# ESP_NOW_uni_FULL.net
KiCad netlist of a schematic drawn in EAGLE
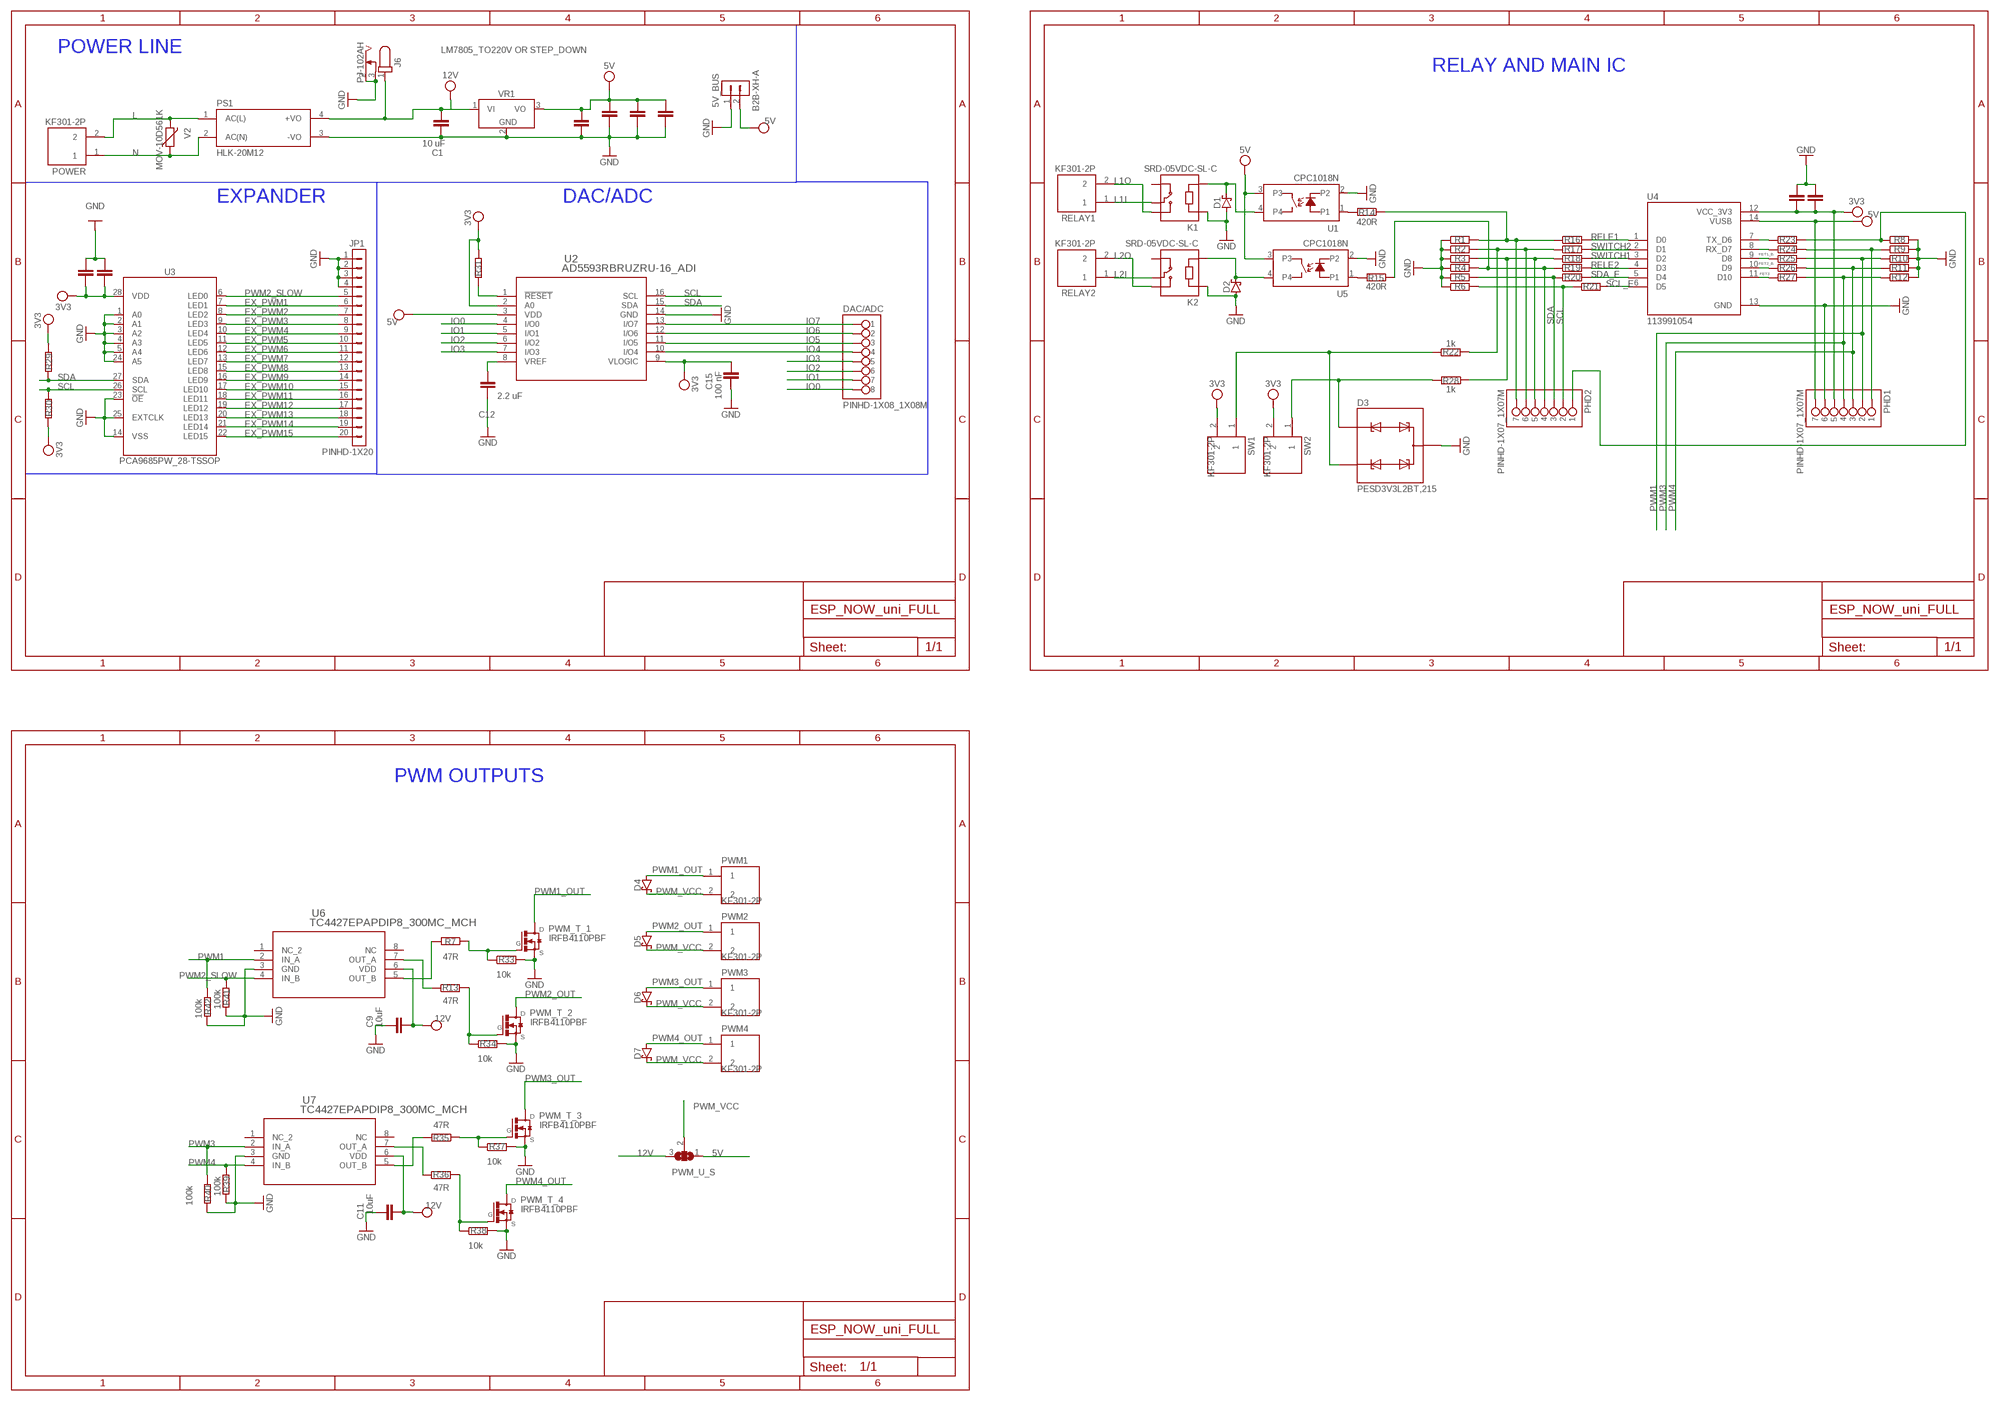
[diagram p0: schematic, sheet 1]

(export (version "E")
  (design (tool "Eeschema 10.0.6"))
  (components
    (comp (ref "5V_BUS")
      (value "B2B-XH-A")
      (footprint "eagle-import:B2B-XH-A")
      (fields (field (name "MANUFACTURER") "JST Sales America Inc."))
      (libsource (lib "eagle-import") (part "B2B-XH-A"))
    )
    (comp (ref "C1")
      (value "10 uF")
      (footprint "eagle-import:CAPC2012X110")
      (libsource (lib "eagle-import") (part "CCHIP-0805(2012-METRIC)_"))
    )
    (comp (ref "C2")
      (value "0.1uF")
      (footprint "eagle-import:CAPC2012X110")
      (libsource (lib "eagle-import") (part "CCHIP-0805(2012-METRIC)_"))
    )
    (comp (ref "C3")
      (value "10uF")
      (footprint "eagle-import:CAPC2012X110")
      (libsource (lib "eagle-import") (part "CCHIP-0805(2012-METRIC)_"))
    )
    (comp (ref "C4")
      (value "10uF")
      (footprint "eagle-import:CAPC2012X110")
      (libsource (lib "eagle-import") (part "CCHIP-0805(2012-METRIC)_"))
    )
    (comp (ref "C5")
      (value "10uF")
      (footprint "eagle-import:CAPC2012X110")
      (libsource (lib "eagle-import") (part "CCHIP-0805(2012-METRIC)_"))
    )
    (comp (ref "C6")
      (value "10uF")
      (footprint "eagle-import:CAPC2012X110")
      (libsource (lib "eagle-import") (part "CCHIP-0805(2012-METRIC)_"))
    )
    (comp (ref "C7")
      (value "10uF")
      (footprint "eagle-import:CAPC2012X110")
      (libsource (lib "eagle-import") (part "CCHIP-0805(2012-METRIC)_"))
    )
    (comp (ref "C8")
      (value "10uF")
      (footprint "eagle-import:CAPC2012X110")
      (libsource (lib "eagle-import") (part "CCHIP-0805(2012-METRIC)_"))
    )
    (comp (ref "C9")
      (value "10uF")
      (footprint "eagle-import:CAPC2012X110")
      (libsource (lib "eagle-import") (part "CCHIP-0805(2012-METRIC)_"))
    )
    (comp (ref "C10")
      (value "10uF")
      (footprint "eagle-import:CAPC2012X110")
      (libsource (lib "eagle-import") (part "CCHIP-0805(2012-METRIC)_"))
    )
    (comp (ref "C11")
      (value "10uF")
      (footprint "eagle-import:CAPC2012X110")
      (libsource (lib "eagle-import") (part "CCHIP-0805(2012-METRIC)_"))
    )
    (comp (ref "C12")
      (value "2.2 uF")
      (footprint "eagle-import:CAPC2012X110")
      (libsource (lib "eagle-import") (part "CCHIP-0805(2012-METRIC)_"))
    )
    (comp (ref "C15")
      (value "100 nF")
      (footprint "eagle-import:CAPC2012X110")
      (libsource (lib "eagle-import") (part "CCHIP-0805(2012-METRIC)_"))
    )
    (comp (ref "D1")
      (value "SCHOTTKY_MBR0520LT1GDO-219")
      (footprint "eagle-import:SODFL3718X115")
      (fields (field (name "MANUFACTURER") "onsemi") (field (name "MPN") "MBR0520LT1G"))
      (libsource (lib "eagle-import") (part "SCHOTTKY_DO-219MBR0520LT1G"))
    )
    (comp (ref "D2")
      (value "SCHOTTKY_MBR0520LT1GDO-219")
      (footprint "eagle-import:SODFL3718X115")
      (fields (field (name "MANUFACTURER") "onsemi") (field (name "MPN") "MBR0520LT1G"))
      (libsource (lib "eagle-import") (part "SCHOTTKY_DO-219MBR0520LT1G"))
    )
    (comp (ref "D3")
      (value "PESD3V3L2BT,215")
      (footprint "eagle-import:SOT95P230X110-3N")
      (fields (field (name "MF") "NXP Semiconductors"))
      (libsource (lib "eagle-import") (part "PESD3V3L2BT,215"))
    )
    (comp (ref "D4")
      (value "SCHOTTKY_MBR0520LT1GDO-219")
      (footprint "eagle-import:SODFL3718X115")
      (fields (field (name "MANUFACTURER") "onsemi") (field (name "MPN") "MBR0520LT1G"))
      (libsource (lib "eagle-import") (part "SCHOTTKY_DO-219MBR0520LT1G"))
    )
    (comp (ref "D5")
      (value "SCHOTTKY_MBR0520LT1GDO-219")
      (footprint "eagle-import:SODFL3718X115")
      (fields (field (name "MANUFACTURER") "onsemi") (field (name "MPN") "MBR0520LT1G"))
      (libsource (lib "eagle-import") (part "SCHOTTKY_DO-219MBR0520LT1G"))
    )
    (comp (ref "D6")
      (value "SCHOTTKY_MBR0520LT1GDO-219")
      (footprint "eagle-import:SODFL3718X115")
      (fields (field (name "MANUFACTURER") "onsemi") (field (name "MPN") "MBR0520LT1G"))
      (libsource (lib "eagle-import") (part "SCHOTTKY_DO-219MBR0520LT1G"))
    )
    (comp (ref "D7")
      (value "SCHOTTKY_MBR0520LT1GDO-219")
      (footprint "eagle-import:SODFL3718X115")
      (fields (field (name "MANUFACTURER") "onsemi") (field (name "MPN") "MBR0520LT1G"))
      (libsource (lib "eagle-import") (part "SCHOTTKY_DO-219MBR0520LT1G"))
    )
    (comp (ref "DAC/ADC")
      (value "PINHD-1X08_1X08M")
      (footprint "eagle-import:1X08")
      (libsource (lib "eagle-import") (part "PINHD-1X08_1X08M"))
    )
    (comp (ref "J6")
      (value "PJ-102AH")
      (footprint "eagle-import:PJ-102AH")
      (fields (field (name "MANUFACTURER") "Same Sky"))
      (libsource (lib "eagle-import") (part "PJ-102AH"))
    )
    (comp (ref "JP1")
      (value "PINHD-1X20")
      (footprint "eagle-import:1X20")
      (libsource (lib "eagle-import") (part "PINHD-1X20"))
    )
    (comp (ref "K1")
      (value "SRD-05VDC-SL-C")
      (footprint "eagle-import:RELAY_SRD-05VDC-SL-C")
      (fields (field (name "MF") "Songle Relay"))
      (libsource (lib "eagle-import") (part "SRD-05VDC-SL-C"))
    )
    (comp (ref "K2")
      (value "SRD-05VDC-SL-C")
      (footprint "eagle-import:RELAY_SRD-05VDC-SL-C")
      (fields (field (name "MF") "Songle Relay"))
      (libsource (lib "eagle-import") (part "SRD-05VDC-SL-C"))
    )
    (comp (ref "PHD1")
      (value "PINHD-1X07_1X07M")
      (footprint "eagle-import:1X07")
      (libsource (lib "eagle-import") (part "PINHD-1X07_1X07M"))
    )
    (comp (ref "PHD2")
      (value "PINHD-1X07_1X07M")
      (footprint "eagle-import:1X07")
      (libsource (lib "eagle-import") (part "PINHD-1X07_1X07M"))
    )
    (comp (ref "POWER")
      (value "KF301-2P")
      (footprint "eagle-import:HANDSON_KF301-2P")
      (fields (field (name "MF") "Handson Technology"))
      (libsource (lib "eagle-import") (part "KF301-2P"))
    )
    (comp (ref "PS1")
      (value "HLK-20M12")
      (footprint "eagle-import:CONV_HLK-20M12")
      (fields (field (name "MF") "Hi-link"))
      (libsource (lib "eagle-import") (part "HLK-20M12"))
    )
    (comp (ref "PWM1")
      (value "KF301-2P")
      (footprint "eagle-import:HANDSON_KF301-2P")
      (fields (field (name "MF") "Handson Technology"))
      (libsource (lib "eagle-import") (part "KF301-2P"))
    )
    (comp (ref "PWM2")
      (value "KF301-2P")
      (footprint "eagle-import:HANDSON_KF301-2P")
      (fields (field (name "MF") "Handson Technology"))
      (libsource (lib "eagle-import") (part "KF301-2P"))
    )
    (comp (ref "PWM3")
      (value "KF301-2P")
      (footprint "eagle-import:HANDSON_KF301-2P")
      (fields (field (name "MF") "Handson Technology"))
      (libsource (lib "eagle-import") (part "KF301-2P"))
    )
    (comp (ref "PWM4")
      (value "KF301-2P")
      (footprint "eagle-import:HANDSON_KF301-2P")
      (fields (field (name "MF") "Handson Technology"))
      (libsource (lib "eagle-import") (part "KF301-2P"))
    )
    (comp (ref "PWM_T_1")
      (value "IRFB4110PBF")
      (footprint "eagle-import:TO220V")
      (fields (field (name "MF") "Infineon Technologies") (field (name "MP") "IRL540N"))
      (libsource (lib "eagle-import") (part "IRL540N"))
    )
    (comp (ref "PWM_T_2")
      (value "IRFB4110PBF")
      (footprint "eagle-import:TO220V")
      (fields (field (name "MF") "Infineon Technologies") (field (name "MP") "IRL540N"))
      (libsource (lib "eagle-import") (part "IRL540N"))
    )
    (comp (ref "PWM_T_3")
      (value "IRFB4110PBF")
      (footprint "eagle-import:TO220V")
      (fields (field (name "MF") "Infineon Technologies") (field (name "MP") "IRL540N"))
      (libsource (lib "eagle-import") (part "IRL540N"))
    )
    (comp (ref "PWM_T_4")
      (value "IRFB4110PBF")
      (footprint "eagle-import:TO220V")
      (fields (field (name "MF") "Infineon Technologies") (field (name "MP") "IRL540N"))
      (libsource (lib "eagle-import") (part "IRL540N"))
    )
    (comp (ref "PWM_U_S")
      (value "SJ2W")
      (footprint "eagle-import:SJ_2")
      (libsource (lib "eagle-import") (part "SJ2W"))
    )
    (comp (ref "R1")
      (value "R_CHIP-0603(1608-METRIC)")
      (footprint "eagle-import:RESC1608X60")
      (libsource (lib "eagle-import") (part "RCHIP-0603(1608-METRIC)_"))
    )
    (comp (ref "R2")
      (value "R_CHIP-0603(1608-METRIC)")
      (footprint "eagle-import:RESC1608X60")
      (libsource (lib "eagle-import") (part "RCHIP-0603(1608-METRIC)_"))
    )
    (comp (ref "R3")
      (value "R_CHIP-0603(1608-METRIC)")
      (footprint "eagle-import:RESC1608X60")
      (libsource (lib "eagle-import") (part "RCHIP-0603(1608-METRIC)_"))
    )
    (comp (ref "R4")
      (value "R_CHIP-0603(1608-METRIC)")
      (footprint "eagle-import:RESC1608X60")
      (libsource (lib "eagle-import") (part "RCHIP-0603(1608-METRIC)_"))
    )
    (comp (ref "R5")
      (value "R_CHIP-0603(1608-METRIC)")
      (footprint "eagle-import:RESC1608X60")
      (libsource (lib "eagle-import") (part "RCHIP-0603(1608-METRIC)_"))
    )
    (comp (ref "R6")
      (value "R_CHIP-0603(1608-METRIC)")
      (footprint "eagle-import:RESC1608X60")
      (libsource (lib "eagle-import") (part "RCHIP-0603(1608-METRIC)_"))
    )
    (comp (ref "R7")
      (value "47R")
      (footprint "eagle-import:RESC1608X60")
      (libsource (lib "eagle-import") (part "RCHIP-0603(1608-METRIC)_"))
    )
    (comp (ref "R8")
      (value "R_CHIP-0603(1608-METRIC)")
      (footprint "eagle-import:RESC1608X60")
      (libsource (lib "eagle-import") (part "RCHIP-0603(1608-METRIC)_"))
    )
    (comp (ref "R9")
      (value "R_CHIP-0603(1608-METRIC)")
      (footprint "eagle-import:RESC1608X60")
      (libsource (lib "eagle-import") (part "RCHIP-0603(1608-METRIC)_"))
    )
    (comp (ref "R10")
      (value "R_CHIP-0603(1608-METRIC)")
      (footprint "eagle-import:RESC1608X60")
      (libsource (lib "eagle-import") (part "RCHIP-0603(1608-METRIC)_"))
    )
    (comp (ref "R11")
      (value "R_CHIP-0603(1608-METRIC)")
      (footprint "eagle-import:RESC1608X60")
      (libsource (lib "eagle-import") (part "RCHIP-0603(1608-METRIC)_"))
    )
    (comp (ref "R12")
      (value "R_CHIP-0603(1608-METRIC)")
      (footprint "eagle-import:RESC1608X60")
      (libsource (lib "eagle-import") (part "RCHIP-0603(1608-METRIC)_"))
    )
    (comp (ref "R13")
      (value "47R")
      (footprint "eagle-import:RESC1608X60")
      (libsource (lib "eagle-import") (part "RCHIP-0603(1608-METRIC)_"))
    )
    (comp (ref "R14")
      (value "420R")
      (footprint "eagle-import:RESC1608X60")
      (libsource (lib "eagle-import") (part "RCHIP-0603(1608-METRIC)_"))
    )
    (comp (ref "R15")
      (value "420R")
      (footprint "eagle-import:RESC1608X60")
      (libsource (lib "eagle-import") (part "RCHIP-0603(1608-METRIC)_"))
    )
    (comp (ref "R16")
      (value "R_CHIP-0603(1608-METRIC)")
      (footprint "eagle-import:RESC1608X60")
      (libsource (lib "eagle-import") (part "RCHIP-0603(1608-METRIC)_"))
    )
    (comp (ref "R17")
      (value "R_CHIP-0603(1608-METRIC)")
      (footprint "eagle-import:RESC1608X60")
      (libsource (lib "eagle-import") (part "RCHIP-0603(1608-METRIC)_"))
    )
    (comp (ref "R18")
      (value "R_CHIP-0603(1608-METRIC)")
      (footprint "eagle-import:RESC1608X60")
      (libsource (lib "eagle-import") (part "RCHIP-0603(1608-METRIC)_"))
    )
    (comp (ref "R19")
      (value "R_CHIP-0603(1608-METRIC)")
      (footprint "eagle-import:RESC1608X60")
      (libsource (lib "eagle-import") (part "RCHIP-0603(1608-METRIC)_"))
    )
    (comp (ref "R20")
      (value "R_CHIP-0603(1608-METRIC)")
      (footprint "eagle-import:RESC1608X60")
      (libsource (lib "eagle-import") (part "RCHIP-0603(1608-METRIC)_"))
    )
    (comp (ref "R21")
      (value "R_CHIP-0603(1608-METRIC)")
      (footprint "eagle-import:RESC1608X60")
      (libsource (lib "eagle-import") (part "RCHIP-0603(1608-METRIC)_"))
    )
    (comp (ref "R22")
      (value "1k")
      (footprint "eagle-import:RESC1608X60")
      (libsource (lib "eagle-import") (part "RCHIP-0603(1608-METRIC)_"))
    )
    (comp (ref "R23")
      (value "R_CHIP-0603(1608-METRIC)")
      (footprint "eagle-import:RESC1608X60")
      (libsource (lib "eagle-import") (part "RCHIP-0603(1608-METRIC)_"))
    )
    (comp (ref "R24")
      (value "R_CHIP-0603(1608-METRIC)")
      (footprint "eagle-import:RESC1608X60")
      (libsource (lib "eagle-import") (part "RCHIP-0603(1608-METRIC)_"))
    )
    (comp (ref "R25")
      (value "R_CHIP-0603(1608-METRIC)")
      (footprint "eagle-import:RESC1608X60")
      (libsource (lib "eagle-import") (part "RCHIP-0603(1608-METRIC)_"))
    )
    (comp (ref "R26")
      (value "R_CHIP-0603(1608-METRIC)")
      (footprint "eagle-import:RESC1608X60")
      (libsource (lib "eagle-import") (part "RCHIP-0603(1608-METRIC)_"))
    )
    (comp (ref "R27")
      (value "R_CHIP-0603(1608-METRIC)")
      (footprint "eagle-import:RESC1608X60")
      (libsource (lib "eagle-import") (part "RCHIP-0603(1608-METRIC)_"))
    )
    (comp (ref "R28")
      (value "1k")
      (footprint "eagle-import:RESC1608X60")
      (libsource (lib "eagle-import") (part "RCHIP-0603(1608-METRIC)_"))
    )
    (comp (ref "R29")
      (value "R_CHIP-0603(1608-METRIC)")
      (footprint "eagle-import:RESC1608X60")
      (libsource (lib "eagle-import") (part "RCHIP-0603(1608-METRIC)_"))
    )
    (comp (ref "R30")
      (value "R_CHIP-0603(1608-METRIC)")
      (footprint "eagle-import:RESC1608X60")
      (libsource (lib "eagle-import") (part "RCHIP-0603(1608-METRIC)_"))
    )
    (comp (ref "R31")
      (value "R_CHIP-0603(1608-METRIC)")
      (footprint "eagle-import:RESC1608X60")
      (libsource (lib "eagle-import") (part "RCHIP-0603(1608-METRIC)_"))
    )
    (comp (ref "R33")
      (value "10k")
      (footprint "eagle-import:RESC1608X60")
      (libsource (lib "eagle-import") (part "RCHIP-0603(1608-METRIC)_"))
    )
    (comp (ref "R34")
      (value "10k")
      (footprint "eagle-import:RESC1608X60")
      (libsource (lib "eagle-import") (part "RCHIP-0603(1608-METRIC)_"))
    )
    (comp (ref "R35")
      (value "47R")
      (footprint "eagle-import:RESC1608X60")
      (libsource (lib "eagle-import") (part "RCHIP-0603(1608-METRIC)_"))
    )
    (comp (ref "R36")
      (value "47R")
      (footprint "eagle-import:RESC1608X60")
      (libsource (lib "eagle-import") (part "RCHIP-0603(1608-METRIC)_"))
    )
    (comp (ref "R37")
      (value "10k")
      (footprint "eagle-import:RESC1608X60")
      (libsource (lib "eagle-import") (part "RCHIP-0603(1608-METRIC)_"))
    )
    (comp (ref "R38")
      (value "10k")
      (footprint "eagle-import:RESC1608X60")
      (libsource (lib "eagle-import") (part "RCHIP-0603(1608-METRIC)_"))
    )
    (comp (ref "R39")
      (value "100k")
      (footprint "eagle-import:RESC1608X60")
      (libsource (lib "eagle-import") (part "RCHIP-0603(1608-METRIC)_"))
    )
    (comp (ref "R40")
      (value "100k")
      (footprint "eagle-import:RESC1608X60")
      (libsource (lib "eagle-import") (part "RCHIP-0603(1608-METRIC)_"))
    )
    (comp (ref "R41")
      (value "100k")
      (footprint "eagle-import:RESC1608X60")
      (libsource (lib "eagle-import") (part "RCHIP-0603(1608-METRIC)_"))
    )
    (comp (ref "R42")
      (value "100k")
      (footprint "eagle-import:RESC1608X60")
      (libsource (lib "eagle-import") (part "RCHIP-0603(1608-METRIC)_"))
    )
    (comp (ref "RELAY1")
      (value "KF301-2P")
      (footprint "eagle-import:HANDSON_KF301-2P")
      (fields (field (name "MF") "Handson Technology"))
      (libsource (lib "eagle-import") (part "KF301-2P"))
    )
    (comp (ref "RELAY2")
      (value "KF301-2P")
      (footprint "eagle-import:HANDSON_KF301-2P")
      (fields (field (name "MF") "Handson Technology"))
      (libsource (lib "eagle-import") (part "KF301-2P"))
    )
    (comp (ref "SW1")
      (value "KF301-2P")
      (footprint "eagle-import:HANDSON_KF301-2P")
      (fields (field (name "MF") "Handson Technology"))
      (libsource (lib "eagle-import") (part "KF301-2P"))
    )
    (comp (ref "SW2")
      (value "KF301-2P")
      (footprint "eagle-import:HANDSON_KF301-2P")
      (fields (field (name "MF") "Handson Technology"))
      (libsource (lib "eagle-import") (part "KF301-2P"))
    )
    (comp (ref "U1")
      (value "CPC1018N")
      (footprint "eagle-import:CLARE_SO4")
      (fields (field (name "MF") "IXYS Integrated Circuits"))
      (libsource (lib "eagle-import") (part "CPC1018N"))
    )
    (comp (ref "U2")
      (value "AD5593RBRUZRU-16_ADI")
      (footprint "eagle-import:RU-16_ADI")
      (fields
        (field (name "MANUFACTURER_PART_NUMBER") "AD5593RBRUZ")
        (field (name "COPYRIGHT") "Copyright (C) 2026 Ultra Librarian. All rights reserved.")
      )
      (libsource (lib "eagle-import") (part "AD5593RBRUZRU-16_ADI"))
    )
    (comp (ref "U3")
      (value "PCA9685PW_28-TSSOP")
      (footprint "eagle-import:SOP65P640X110-28")
      (fields (field (name "MANUFACTURER") "NXP USA Inc.") (field (name "MPN") "PCA9685PW118"))
      (libsource (lib "eagle-import") (part "PCA9685PW_28-TSSOP"))
    )
    (comp (ref "U4")
      (value "113991054")
      (footprint "eagle-import:MODULE_113991054")
      (fields (field (name "MF") "Seeed Technology Co., Ltd"))
      (libsource (lib "eagle-import") (part "113991054"))
    )
    (comp (ref "U5")
      (value "CPC1018N")
      (footprint "eagle-import:CLARE_SO4")
      (fields (field (name "MF") "IXYS Integrated Circuits"))
      (libsource (lib "eagle-import") (part "CPC1018N"))
    )
    (comp (ref "U6")
      (value "TC4427EPAPDIP8_300MC_MCH")
      (footprint "eagle-import:PDIP8_300MC_MCH")
      (fields
        (field (name "MANUFACTURER_PART_NUMBER") "TC4427EPA")
        (field (name "COPYRIGHT") "Copyright (C) 2026 Ultra Librarian. All rights reserved.")
      )
      (libsource (lib "eagle-import") (part "TC4427EPAPDIP8_300MC_MCH"))
    )
    (comp (ref "U7")
      (value "TC4427EPAPDIP8_300MC_MCH")
      (footprint "eagle-import:PDIP8_300MC_MCH")
      (fields
        (field (name "MANUFACTURER_PART_NUMBER") "TC4427EPA")
        (field (name "COPYRIGHT") "Copyright (C) 2026 Ultra Librarian. All rights reserved.")
      )
      (libsource (lib "eagle-import") (part "TC4427EPAPDIP8_300MC_MCH"))
    )
    (comp (ref "V2")
      (value "MOV-10D561K")
      (footprint "eagle-import:MOV-10D561")
      (fields (field (name "MF") "Bourns"))
      (libsource (lib "eagle-import") (part "MOV-10D561K"))
    )
    (comp (ref "VR1")
      (value "LM7805_TO220V OR STEP_DOWN")
      (footprint "eagle-import:TO220V")
      (libsource (lib "eagle-import") (part "LM7805_TO220V"))
    )
  )
  (nets
    (net (code "1") (name "/EX_PWM1") (class "Default")
      (node (ref "JP1") (pin "6") (pinfunction "6_6") (pintype "passive"))
      (node (ref "U3") (pin "7") (pinfunction "LED1_7") (pintype "passive"))
    )
    (net (code "2") (name "/EX_PWM2") (class "Default")
      (node (ref "JP1") (pin "7") (pinfunction "7_7") (pintype "passive"))
      (node (ref "U3") (pin "8") (pinfunction "LED2_8") (pintype "passive"))
    )
    (net (code "3") (name "/EX_PWM3") (class "Default")
      (node (ref "JP1") (pin "8") (pinfunction "8_8") (pintype "passive"))
      (node (ref "U3") (pin "9") (pinfunction "LED3_9") (pintype "passive"))
    )
    (net (code "4") (name "/EX_PWM4") (class "Default")
      (node (ref "JP1") (pin "9") (pinfunction "9_9") (pintype "passive"))
      (node (ref "U3") (pin "10") (pinfunction "LED4_10") (pintype "passive"))
    )
    (net (code "5") (name "/EX_PWM5") (class "Default")
      (node (ref "JP1") (pin "10") (pinfunction "10_10") (pintype "passive"))
      (node (ref "U3") (pin "11") (pinfunction "LED5_11") (pintype "passive"))
    )
    (net (code "6") (name "/EX_PWM6") (class "Default")
      (node (ref "JP1") (pin "11") (pinfunction "11_11") (pintype "passive"))
      (node (ref "U3") (pin "12") (pinfunction "LED6_12") (pintype "passive"))
    )
    (net (code "7") (name "/EX_PWM7") (class "Default")
      (node (ref "JP1") (pin "12") (pinfunction "12_12") (pintype "passive"))
      (node (ref "U3") (pin "13") (pinfunction "LED7_13") (pintype "passive"))
    )
    (net (code "8") (name "/EX_PWM8") (class "Default")
      (node (ref "JP1") (pin "13") (pinfunction "13_13") (pintype "passive"))
      (node (ref "U3") (pin "15") (pinfunction "LED8_15") (pintype "passive"))
    )
    (net (code "9") (name "/EX_PWM9") (class "Default")
      (node (ref "JP1") (pin "14") (pinfunction "14_14") (pintype "passive"))
      (node (ref "U3") (pin "16") (pinfunction "LED9_16") (pintype "passive"))
    )
    (net (code "10") (name "/EX_PWM10") (class "Default")
      (node (ref "JP1") (pin "15") (pinfunction "15_15") (pintype "passive"))
      (node (ref "U3") (pin "17") (pinfunction "LED10_17") (pintype "passive"))
    )
    (net (code "11") (name "/EX_PWM11") (class "Default")
      (node (ref "JP1") (pin "16") (pinfunction "16_16") (pintype "passive"))
      (node (ref "U3") (pin "18") (pinfunction "LED11_18") (pintype "passive"))
    )
    (net (code "12") (name "/EX_PWM12") (class "Default")
      (node (ref "JP1") (pin "17") (pinfunction "17_17") (pintype "passive"))
      (node (ref "U3") (pin "19") (pinfunction "LED12_19") (pintype "passive"))
    )
    (net (code "13") (name "/EX_PWM13") (class "Default")
      (node (ref "JP1") (pin "18") (pinfunction "18_18") (pintype "passive"))
      (node (ref "U3") (pin "20") (pinfunction "LED13_20") (pintype "passive"))
    )
    (net (code "14") (name "/EX_PWM14") (class "Default")
      (node (ref "JP1") (pin "19") (pinfunction "19_19") (pintype "passive"))
      (node (ref "U3") (pin "21") (pinfunction "LED14_21") (pintype "passive"))
    )
    (net (code "15") (name "/EX_PWM15") (class "Default")
      (node (ref "JP1") (pin "20") (pinfunction "20_20") (pintype "passive"))
      (node (ref "U3") (pin "22") (pinfunction "LED15_22") (pintype "passive"))
    )
    (net (code "16") (name "/FET1_B") (class "Default")
      (node (ref "R25") (pin "1") (pinfunction "1_1") (pintype "passive"))
      (node (ref "U4") (pin "9") (pinfunction "D8_9") (pintype "bidirectional"))
    )
    (net (code "17") (name "/FET2_B") (class "Default")
      (node (ref "R26") (pin "1") (pinfunction "1_1") (pintype "passive"))
      (node (ref "U4") (pin "10") (pinfunction "D9_10") (pintype "bidirectional"))
    )
    (net (code "18") (name "/FET3") (class "Default")
      (node (ref "R27") (pin "1") (pinfunction "1_1") (pintype "passive"))
      (node (ref "U4") (pin "11") (pinfunction "D10_11") (pintype "bidirectional"))
    )
    (net (code "19") (name "/IO0") (class "Default")
      (node (ref "DAC/ADC") (pin "8") (pinfunction "8_8") (pintype "bidirectional"))
      (node (ref "U2") (pin "4") (pinfunction "I/O0_4") (pintype "passive"))
    )
    (net (code "20") (name "/IO1") (class "Default")
      (node (ref "DAC/ADC") (pin "7") (pinfunction "7_7") (pintype "bidirectional"))
      (node (ref "U2") (pin "5") (pinfunction "I/O1_5") (pintype "passive"))
    )
    (net (code "21") (name "/IO2") (class "Default")
      (node (ref "DAC/ADC") (pin "6") (pinfunction "6_6") (pintype "bidirectional"))
      (node (ref "U2") (pin "6") (pinfunction "I/O2_6") (pintype "passive"))
    )
    (net (code "22") (name "/IO3") (class "Default")
      (node (ref "DAC/ADC") (pin "5") (pinfunction "5_5") (pintype "bidirectional"))
      (node (ref "U2") (pin "7") (pinfunction "I/O3_7") (pintype "passive"))
    )
    (net (code "23") (name "/IO4") (class "Default")
      (node (ref "DAC/ADC") (pin "4") (pinfunction "4_4") (pintype "bidirectional"))
      (node (ref "U2") (pin "10") (pinfunction "I/O4_10") (pintype "passive"))
    )
    (net (code "24") (name "/IO5") (class "Default")
      (node (ref "DAC/ADC") (pin "3") (pinfunction "3_3") (pintype "bidirectional"))
      (node (ref "U2") (pin "11") (pinfunction "I/O5_11") (pintype "passive"))
    )
    (net (code "25") (name "/IO6") (class "Default")
      (node (ref "DAC/ADC") (pin "2") (pinfunction "2_2") (pintype "bidirectional"))
      (node (ref "U2") (pin "12") (pinfunction "I/O6_12") (pintype "passive"))
    )
    (net (code "26") (name "/IO7") (class "Default")
      (node (ref "DAC/ADC") (pin "1") (pinfunction "1_1") (pintype "bidirectional"))
      (node (ref "U2") (pin "13") (pinfunction "I/O7_13") (pintype "passive"))
    )
    (net (code "27") (name "/L") (class "Default")
      (node (ref "POWER") (pin "2") (pinfunction "2_2") (pintype "passive"))
      (node (ref "PS1") (pin "1") (pinfunction "AC(L)_1") (pintype "input"))
      (node (ref "V2") (pin "2") (pinfunction "2_2") (pintype "passive"))
    )
    (net (code "28") (name "/L1I") (class "Default")
      (node (ref "K1") (pin "COM") (pinfunction "COM_COM") (pintype "passive"))
      (node (ref "RELAY1") (pin "1") (pinfunction "1_1") (pintype "passive"))
    )
    (net (code "29") (name "/L1O") (class "Default")
      (node (ref "K1") (pin "NO") (pinfunction "NO_NO") (pintype "passive"))
      (node (ref "RELAY1") (pin "2") (pinfunction "2_2") (pintype "passive"))
    )
    (net (code "30") (name "/L2I") (class "Default")
      (node (ref "K2") (pin "COM") (pinfunction "COM_COM") (pintype "passive"))
      (node (ref "RELAY2") (pin "1") (pinfunction "1_1") (pintype "passive"))
    )
    (net (code "31") (name "/L2O") (class "Default")
      (node (ref "K2") (pin "NO") (pinfunction "NO_NO") (pintype "passive"))
      (node (ref "RELAY2") (pin "2") (pinfunction "2_2") (pintype "passive"))
    )
    (net (code "32") (name "/N") (class "Default")
      (node (ref "POWER") (pin "1") (pinfunction "1_1") (pintype "passive"))
      (node (ref "PS1") (pin "2") (pinfunction "AC(N)_2") (pintype "input"))
      (node (ref "V2") (pin "1") (pinfunction "1_1") (pintype "passive"))
    )
    (net (code "33") (name "/PWM1") (class "Default")
      (node (ref "PHD1") (pin "2") (pinfunction "2_2") (pintype "bidirectional"))
      (node (ref "R10") (pin "1") (pinfunction "1_1") (pintype "passive"))
      (node (ref "R25") (pin "2") (pinfunction "2_2") (pintype "passive"))
      (node (ref "R42") (pin "1") (pinfunction "1_1") (pintype "passive"))
      (node (ref "U6") (pin "2") (pinfunction "IN_A_2") (pintype "passive"))
    )
    (net (code "34") (name "/PWM1_OUT") (class "Default")
      (node (ref "D4") (pin "2") (pinfunction "A_2") (pintype "passive"))
      (node (ref "PWM1") (pin "1") (pinfunction "1_1") (pintype "passive"))
      (node (ref "PWM_T_1") (pin "2") (pinfunction "D_2") (pintype "passive"))
    )
    (net (code "35") (name "/PWM2_OUT") (class "Default")
      (node (ref "D5") (pin "2") (pinfunction "A_2") (pintype "passive"))
      (node (ref "PWM2") (pin "1") (pinfunction "1_1") (pintype "passive"))
      (node (ref "PWM_T_2") (pin "2") (pinfunction "D_2") (pintype "passive"))
    )
    (net (code "36") (name "/PWM2_SLOW") (class "Default")
      (node (ref "JP1") (pin "5") (pinfunction "5_5") (pintype "passive"))
      (node (ref "R41") (pin "1") (pinfunction "1_1") (pintype "passive"))
      (node (ref "U3") (pin "6") (pinfunction "LED0_6") (pintype "passive"))
      (node (ref "U6") (pin "4") (pinfunction "IN_B_4") (pintype "passive"))
    )
    (net (code "37") (name "/PWM3") (class "Default")
      (node (ref "PHD1") (pin "4") (pinfunction "4_4") (pintype "bidirectional"))
      (node (ref "R12") (pin "1") (pinfunction "1_1") (pintype "passive"))
      (node (ref "R27") (pin "2") (pinfunction "2_2") (pintype "passive"))
      (node (ref "R40") (pin "1") (pinfunction "1_1") (pintype "passive"))
      (node (ref "U7") (pin "2") (pinfunction "IN_A_2") (pintype "passive"))
    )
    (net (code "38") (name "/PWM3_OUT") (class "Default")
      (node (ref "D6") (pin "2") (pinfunction "A_2") (pintype "passive"))
      (node (ref "PWM3") (pin "1") (pinfunction "1_1") (pintype "passive"))
      (node (ref "PWM_T_3") (pin "2") (pinfunction "D_2") (pintype "passive"))
    )
    (net (code "39") (name "/PWM4") (class "Default")
      (node (ref "PHD1") (pin "3") (pinfunction "3_3") (pintype "bidirectional"))
      (node (ref "R11") (pin "1") (pinfunction "1_1") (pintype "passive"))
      (node (ref "R26") (pin "2") (pinfunction "2_2") (pintype "passive"))
      (node (ref "R39") (pin "1") (pinfunction "1_1") (pintype "passive"))
      (node (ref "U7") (pin "4") (pinfunction "IN_B_4") (pintype "passive"))
    )
    (net (code "40") (name "/PWM4_OUT") (class "Default")
      (node (ref "D7") (pin "2") (pinfunction "A_2") (pintype "passive"))
      (node (ref "PWM4") (pin "1") (pinfunction "1_1") (pintype "passive"))
      (node (ref "PWM_T_4") (pin "2") (pinfunction "D_2") (pintype "passive"))
    )
    (net (code "41") (name "/PWM_VCC") (class "Default")
      (node (ref "D4") (pin "1") (pinfunction "C_1") (pintype "passive"))
      (node (ref "D5") (pin "1") (pinfunction "C_1") (pintype "passive"))
      (node (ref "D6") (pin "1") (pinfunction "C_1") (pintype "passive"))
      (node (ref "D7") (pin "1") (pinfunction "C_1") (pintype "passive"))
      (node (ref "PWM1") (pin "2") (pinfunction "2_2") (pintype "passive"))
      (node (ref "PWM2") (pin "2") (pinfunction "2_2") (pintype "passive"))
      (node (ref "PWM3") (pin "2") (pinfunction "2_2") (pintype "passive"))
      (node (ref "PWM4") (pin "2") (pinfunction "2_2") (pintype "passive"))
      (node (ref "PWM_U_S") (pin "2") (pinfunction "2_2") (pintype "passive"))
    )
    (net (code "42") (name "/RELE1") (class "Default")
      (node (ref "R16") (pin "2") (pinfunction "2_2") (pintype "passive"))
      (node (ref "U4") (pin "1") (pinfunction "D0_1") (pintype "bidirectional"))
    )
    (net (code "43") (name "/RELE2") (class "Default")
      (node (ref "R19") (pin "2") (pinfunction "2_2") (pintype "passive"))
      (node (ref "U4") (pin "4") (pinfunction "D3_4") (pintype "bidirectional"))
    )
    (net (code "44") (name "/SCL") (class "Default")
      (node (ref "PHD2") (pin "2") (pinfunction "2_2") (pintype "bidirectional"))
      (node (ref "R21") (pin "1") (pinfunction "1_1") (pintype "passive"))
      (node (ref "R30") (pin "1") (pinfunction "1_1") (pintype "passive"))
      (node (ref "R6") (pin "2") (pinfunction "2_2") (pintype "passive"))
      (node (ref "U2") (pin "16") (pinfunction "SCL_16") (pintype "passive"))
      (node (ref "U3") (pin "26") (pinfunction "SCL_26") (pintype "passive"))
    )
    (net (code "45") (name "/SCL_E") (class "Default")
      (node (ref "R21") (pin "2") (pinfunction "2_2") (pintype "passive"))
      (node (ref "U4") (pin "6") (pinfunction "D5_6") (pintype "bidirectional"))
    )
    (net (code "46") (name "/SDA") (class "Default")
      (node (ref "PHD2") (pin "3") (pinfunction "3_3") (pintype "bidirectional"))
      (node (ref "R20") (pin "1") (pinfunction "1_1") (pintype "passive"))
      (node (ref "R29") (pin "2") (pinfunction "2_2") (pintype "passive"))
      (node (ref "R5") (pin "2") (pinfunction "2_2") (pintype "passive"))
      (node (ref "U2") (pin "15") (pinfunction "SDA_15") (pintype "passive"))
      (node (ref "U3") (pin "27") (pinfunction "SDA_27") (pintype "passive"))
    )
    (net (code "47") (name "/SDA_E") (class "Default")
      (node (ref "R20") (pin "2") (pinfunction "2_2") (pintype "passive"))
      (node (ref "U4") (pin "5") (pinfunction "D4_5") (pintype "bidirectional"))
    )
    (net (code "48") (name "/SWITCH1") (class "Default")
      (node (ref "R18") (pin "2") (pinfunction "2_2") (pintype "passive"))
      (node (ref "U4") (pin "3") (pinfunction "D2_3") (pintype "bidirectional"))
    )
    (net (code "49") (name "/SWITCH2") (class "Default")
      (node (ref "R17") (pin "2") (pinfunction "2_2") (pintype "passive"))
      (node (ref "U4") (pin "2") (pinfunction "D1_2") (pintype "bidirectional"))
    )
    (net (code "50") (name "3V3") (class "Default")
      (node (ref "C10") (pin "2") (pinfunction "2_2") (pintype "passive"))
      (node (ref "C15") (pin "1") (pinfunction "1_1") (pintype "passive"))
      (node (ref "C6") (pin "2") (pinfunction "2_2") (pintype "passive"))
      (node (ref "C7") (pin "2") (pinfunction "2_2") (pintype "passive"))
      (node (ref "C8") (pin "2") (pinfunction "2_2") (pintype "passive"))
      (node (ref "PHD1") (pin "5") (pinfunction "5_5") (pintype "bidirectional"))
      (node (ref "R29") (pin "1") (pinfunction "1_1") (pintype "passive"))
      (node (ref "R30") (pin "2") (pinfunction "2_2") (pintype "passive"))
      (node (ref "R31") (pin "2") (pinfunction "2_2") (pintype "passive"))
      (node (ref "SW1") (pin "2") (pinfunction "2_2") (pintype "passive"))
      (node (ref "SW2") (pin "2") (pinfunction "2_2") (pintype "passive"))
      (node (ref "U2") (pin "2") (pinfunction "A0_2") (pintype "passive"))
      (node (ref "U2") (pin "9") (pinfunction "VLOGIC_9") (pintype "passive"))
      (node (ref "U3") (pin "28") (pinfunction "VDD_28") (pintype "passive"))
      (node (ref "U4") (pin "12") (pinfunction "VCC_3V3_12") (pintype "power_in"))
    )
    (net (code "51") (name "5V") (class "Default")
      (node (ref "5V_BUS") (pin "2") (pinfunction "2_2") (pintype "passive"))
      (node (ref "C2") (pin "1") (pinfunction "1_1") (pintype "passive"))
      (node (ref "C3") (pin "1") (pinfunction "1_1") (pintype "passive"))
      (node (ref "C4") (pin "1") (pinfunction "1_1") (pintype "passive"))
      (node (ref "C5") (pin "1") (pinfunction "1_1") (pintype "passive"))
      (node (ref "PHD1") (pin "7") (pinfunction "7_7") (pintype "bidirectional"))
      (node (ref "PWM_U_S") (pin "1") (pinfunction "1_1") (pintype "passive"))
      (node (ref "U1") (pin "3") (pinfunction "P3_3") (pintype "passive"))
      (node (ref "U2") (pin "3") (pinfunction "VDD_3") (pintype "passive"))
      (node (ref "U4") (pin "14") (pinfunction "VUSB_14") (pintype "power_in"))
      (node (ref "U5") (pin "3") (pinfunction "P3_3") (pintype "passive"))
      (node (ref "VR1") (pin "3") (pinfunction "VO_3") (pintype "output"))
    )
    (net (code "52") (name "12V") (class "Default")
      (node (ref "C1") (pin "1") (pinfunction "1_1") (pintype "passive"))
      (node (ref "C11") (pin "1") (pinfunction "1_1") (pintype "passive"))
      (node (ref "C9") (pin "1") (pinfunction "1_1") (pintype "passive"))
      (node (ref "J6") (pin "1") (pinfunction "1_1") (pintype "passive"))
      (node (ref "PS1") (pin "4") (pinfunction "+VO_4") (pintype "output"))
      (node (ref "PWM_U_S") (pin "3") (pinfunction "3_3") (pintype "passive"))
      (node (ref "U6") (pin "6") (pinfunction "VDD_6") (pintype "passive"))
      (node (ref "U7") (pin "6") (pinfunction "VDD_6") (pintype "passive"))
      (node (ref "VR1") (pin "1") (pinfunction "VI_1") (pintype "input"))
    )
    (net (code "53") (name "GND") (class "Default")
      (node (ref "5V_BUS") (pin "1") (pinfunction "1_1") (pintype "passive"))
      (node (ref "C1") (pin "2") (pinfunction "2_2") (pintype "passive"))
      (node (ref "C10") (pin "1") (pinfunction "1_1") (pintype "passive"))
      (node (ref "C11") (pin "2") (pinfunction "2_2") (pintype "passive"))
      (node (ref "C12") (pin "2") (pinfunction "2_2") (pintype "passive"))
      (node (ref "C15") (pin "2") (pinfunction "2_2") (pintype "passive"))
      (node (ref "C2") (pin "2") (pinfunction "2_2") (pintype "passive"))
      (node (ref "C3") (pin "2") (pinfunction "2_2") (pintype "passive"))
      (node (ref "C4") (pin "2") (pinfunction "2_2") (pintype "passive"))
      (node (ref "C5") (pin "2") (pinfunction "2_2") (pintype "passive"))
      (node (ref "C6") (pin "1") (pinfunction "1_1") (pintype "passive"))
      (node (ref "C7") (pin "1") (pinfunction "1_1") (pintype "passive"))
      (node (ref "C8") (pin "1") (pinfunction "1_1") (pintype "passive"))
      (node (ref "C9") (pin "2") (pinfunction "2_2") (pintype "passive"))
      (node (ref "D1") (pin "2") (pinfunction "A_2") (pintype "passive"))
      (node (ref "D2") (pin "2") (pinfunction "A_2") (pintype "passive"))
      (node (ref "D3") (pin "3") (pinfunction "CC_3") (pintype "passive"))
      (node (ref "J6") (pin "2") (pinfunction "2_2") (pintype "passive"))
      (node (ref "J6") (pin "3") (pinfunction "3_3") (pintype "passive"))
      (node (ref "JP1") (pin "1") (pinfunction "1_1") (pintype "passive"))
      (node (ref "JP1") (pin "2") (pinfunction "2_2") (pintype "passive"))
      (node (ref "JP1") (pin "3") (pinfunction "3_3") (pintype "passive"))
      (node (ref "JP1") (pin "4") (pinfunction "4_4") (pintype "passive"))
      (node (ref "K1") (pin "A1") (pinfunction "A1_A1") (pintype "passive"))
      (node (ref "K2") (pin "A1") (pinfunction "A1_A1") (pintype "passive"))
      (node (ref "PHD1") (pin "6") (pinfunction "6_6") (pintype "bidirectional"))
      (node (ref "PS1") (pin "3") (pinfunction "-VO_3") (pintype "output"))
      (node (ref "PWM_T_1") (pin "3") (pinfunction "S_3") (pintype "passive"))
      (node (ref "PWM_T_2") (pin "3") (pinfunction "S_3") (pintype "passive"))
      (node (ref "PWM_T_3") (pin "3") (pinfunction "S_3") (pintype "passive"))
      (node (ref "PWM_T_4") (pin "3") (pinfunction "S_3") (pintype "passive"))
      (node (ref "R1") (pin "1") (pinfunction "1_1") (pintype "passive"))
      (node (ref "R10") (pin "2") (pinfunction "2_2") (pintype "passive"))
      (node (ref "R11") (pin "2") (pinfunction "2_2") (pintype "passive"))
      (node (ref "R12") (pin "2") (pinfunction "2_2") (pintype "passive"))
      (node (ref "R2") (pin "1") (pinfunction "1_1") (pintype "passive"))
      (node (ref "R3") (pin "1") (pinfunction "1_1") (pintype "passive"))
      (node (ref "R33") (pin "2") (pinfunction "2_2") (pintype "passive"))
      (node (ref "R34") (pin "2") (pinfunction "2_2") (pintype "passive"))
      (node (ref "R37") (pin "2") (pinfunction "2_2") (pintype "passive"))
      (node (ref "R38") (pin "2") (pinfunction "2_2") (pintype "passive"))
      (node (ref "R39") (pin "2") (pinfunction "2_2") (pintype "passive"))
      (node (ref "R4") (pin "1") (pinfunction "1_1") (pintype "passive"))
      (node (ref "R40") (pin "2") (pinfunction "2_2") (pintype "passive"))
      (node (ref "R41") (pin "2") (pinfunction "2_2") (pintype "passive"))
      (node (ref "R42") (pin "2") (pinfunction "2_2") (pintype "passive"))
      (node (ref "R5") (pin "1") (pinfunction "1_1") (pintype "passive"))
      (node (ref "R6") (pin "1") (pinfunction "1_1") (pintype "passive"))
      (node (ref "R8") (pin "2") (pinfunction "2_2") (pintype "passive"))
      (node (ref "R9") (pin "2") (pinfunction "2_2") (pintype "passive"))
      (node (ref "U1") (pin "2") (pinfunction "P2_2") (pintype "passive"))
      (node (ref "U2") (pin "14") (pinfunction "GND_14") (pintype "passive"))
      (node (ref "U3") (pin "1") (pinfunction "A0_1") (pintype "passive"))
      (node (ref "U3") (pin "14") (pinfunction "VSS_14") (pintype "passive"))
      (node (ref "U3") (pin "2") (pinfunction "A1_2") (pintype "passive"))
      (node (ref "U3") (pin "23") (pinfunction "~{OE}_23") (pintype "passive"))
      (node (ref "U3") (pin "24") (pinfunction "A5_24") (pintype "passive"))
      (node (ref "U3") (pin "25") (pinfunction "EXTCLK_25") (pintype "passive"))
      (node (ref "U3") (pin "3") (pinfunction "A2_3") (pintype "passive"))
      (node (ref "U3") (pin "4") (pinfunction "A3_4") (pintype "passive"))
      (node (ref "U3") (pin "5") (pinfunction "A4_5") (pintype "passive"))
      (node (ref "U4") (pin "13") (pinfunction "GND_13") (pintype "power_in"))
      (node (ref "U5") (pin "2") (pinfunction "P2_2") (pintype "passive"))
      (node (ref "U6") (pin "3") (pinfunction "GND_3") (pintype "passive"))
      (node (ref "U7") (pin "3") (pinfunction "GND_3") (pintype "passive"))
      (node (ref "VR1") (pin "2") (pinfunction "GND_2") (pintype "passive"))
    )
    (net (code "54") (name "Net-(D1-C)") (class "Default")
      (node (ref "D1") (pin "1") (pinfunction "C_1") (pintype "passive"))
      (node (ref "K1") (pin "A2") (pinfunction "A2_A2") (pintype "passive"))
      (node (ref "U1") (pin "4") (pinfunction "P4_4") (pintype "passive"))
    )
    (net (code "55") (name "Net-(D2-C)") (class "Default")
      (node (ref "D2") (pin "1") (pinfunction "C_1") (pintype "passive"))
      (node (ref "K2") (pin "A2") (pinfunction "A2_A2") (pintype "passive"))
      (node (ref "U5") (pin "4") (pinfunction "P4_4") (pintype "passive"))
    )
    (net (code "56") (name "Net-(D3-K1)") (class "Default")
      (node (ref "D3") (pin "1") (pinfunction "K1_1") (pintype "passive"))
      (node (ref "R28") (pin "2") (pinfunction "2_2") (pintype "passive"))
      (node (ref "SW2") (pin "1") (pinfunction "1_1") (pintype "passive"))
    )
    (net (code "57") (name "Net-(D3-K2)") (class "Default")
      (node (ref "D3") (pin "2") (pinfunction "K2_2") (pintype "passive"))
      (node (ref "R22") (pin "1") (pinfunction "1_1") (pintype "passive"))
      (node (ref "SW1") (pin "1") (pinfunction "1_1") (pintype "passive"))
    )
    (net (code "58") (name "Net-(PHD1-Pad1)") (class "Default")
      (node (ref "PHD1") (pin "1") (pinfunction "1_1") (pintype "bidirectional"))
      (node (ref "R24") (pin "2") (pinfunction "2_2") (pintype "passive"))
      (node (ref "R9") (pin "1") (pinfunction "1_1") (pintype "passive"))
    )
    (net (code "59") (name "Net-(PHD2-Pad1)") (class "Default")
      (node (ref "PHD2") (pin "1") (pinfunction "1_1") (pintype "bidirectional"))
      (node (ref "R23") (pin "2") (pinfunction "2_2") (pintype "passive"))
      (node (ref "R8") (pin "1") (pinfunction "1_1") (pintype "passive"))
    )
    (net (code "60") (name "Net-(PHD2-Pad4)") (class "Default")
      (node (ref "PHD2") (pin "4") (pinfunction "4_4") (pintype "bidirectional"))
      (node (ref "R15") (pin "1") (pinfunction "1_1") (pintype "passive"))
      (node (ref "R19") (pin "1") (pinfunction "1_1") (pintype "passive"))
      (node (ref "R4") (pin "2") (pinfunction "2_2") (pintype "passive"))
    )
    (net (code "61") (name "Net-(PHD2-Pad5)") (class "Default")
      (node (ref "PHD2") (pin "5") (pinfunction "5_5") (pintype "bidirectional"))
      (node (ref "R18") (pin "1") (pinfunction "1_1") (pintype "passive"))
      (node (ref "R28") (pin "1") (pinfunction "1_1") (pintype "passive"))
      (node (ref "R3") (pin "2") (pinfunction "2_2") (pintype "passive"))
    )
    (net (code "62") (name "Net-(PHD2-Pad6)") (class "Default")
      (node (ref "PHD2") (pin "6") (pinfunction "6_6") (pintype "bidirectional"))
      (node (ref "R17") (pin "1") (pinfunction "1_1") (pintype "passive"))
      (node (ref "R2") (pin "2") (pinfunction "2_2") (pintype "passive"))
      (node (ref "R22") (pin "2") (pinfunction "2_2") (pintype "passive"))
    )
    (net (code "63") (name "Net-(PHD2-Pad7)") (class "Default")
      (node (ref "PHD2") (pin "7") (pinfunction "7_7") (pintype "bidirectional"))
      (node (ref "R1") (pin "2") (pinfunction "2_2") (pintype "passive"))
      (node (ref "R14") (pin "1") (pinfunction "1_1") (pintype "passive"))
      (node (ref "R16") (pin "1") (pinfunction "1_1") (pintype "passive"))
    )
    (net (code "64") (name "Net-(PWM_T_1-G)") (class "Default")
      (node (ref "PWM_T_1") (pin "1") (pinfunction "G_1") (pintype "passive"))
      (node (ref "R33") (pin "1") (pinfunction "1_1") (pintype "passive"))
      (node (ref "R7") (pin "1") (pinfunction "1_1") (pintype "passive"))
    )
    (net (code "65") (name "Net-(PWM_T_2-G)") (class "Default")
      (node (ref "PWM_T_2") (pin "1") (pinfunction "G_1") (pintype "passive"))
      (node (ref "R13") (pin "2") (pinfunction "2_2") (pintype "passive"))
      (node (ref "R34") (pin "1") (pinfunction "1_1") (pintype "passive"))
    )
    (net (code "66") (name "Net-(PWM_T_3-G)") (class "Default")
      (node (ref "PWM_T_3") (pin "1") (pinfunction "G_1") (pintype "passive"))
      (node (ref "R35") (pin "1") (pinfunction "1_1") (pintype "passive"))
      (node (ref "R37") (pin "1") (pinfunction "1_1") (pintype "passive"))
    )
    (net (code "67") (name "Net-(PWM_T_4-G)") (class "Default")
      (node (ref "PWM_T_4") (pin "1") (pinfunction "G_1") (pintype "passive"))
      (node (ref "R36") (pin "2") (pinfunction "2_2") (pintype "passive"))
      (node (ref "R38") (pin "1") (pinfunction "1_1") (pintype "passive"))
    )
    (net (code "68") (name "Net-(U1-P1)") (class "Default")
      (node (ref "R14") (pin "2") (pinfunction "2_2") (pintype "passive"))
      (node (ref "U1") (pin "1") (pinfunction "P1_1") (pintype "passive"))
    )
    (net (code "69") (name "Net-(U2-VREF)") (class "Default")
      (node (ref "C12") (pin "1") (pinfunction "1_1") (pintype "passive"))
      (node (ref "U2") (pin "8") (pinfunction "VREF_8") (pintype "passive"))
    )
    (net (code "70") (name "Net-(U2-~{RESET})") (class "Default")
      (node (ref "R31") (pin "1") (pinfunction "1_1") (pintype "passive"))
      (node (ref "U2") (pin "1") (pinfunction "~{RESET}_1") (pintype "passive"))
    )
    (net (code "71") (name "Net-(U4-RX_D7)") (class "Default")
      (node (ref "R24") (pin "1") (pinfunction "1_1") (pintype "passive"))
      (node (ref "U4") (pin "8") (pinfunction "RX_D7_8") (pintype "bidirectional"))
    )
    (net (code "72") (name "Net-(U4-TX_D6)") (class "Default")
      (node (ref "R23") (pin "1") (pinfunction "1_1") (pintype "passive"))
      (node (ref "U4") (pin "7") (pinfunction "TX_D6_7") (pintype "bidirectional"))
    )
    (net (code "73") (name "Net-(U5-P1)") (class "Default")
      (node (ref "R15") (pin "2") (pinfunction "2_2") (pintype "passive"))
      (node (ref "U5") (pin "1") (pinfunction "P1_1") (pintype "passive"))
    )
    (net (code "74") (name "Net-(U6-OUT_A)") (class "Default")
      (node (ref "R13") (pin "1") (pinfunction "1_1") (pintype "passive"))
      (node (ref "U6") (pin "7") (pinfunction "OUT_A_7") (pintype "passive"))
    )
    (net (code "75") (name "Net-(U6-OUT_B)") (class "Default")
      (node (ref "R7") (pin "2") (pinfunction "2_2") (pintype "passive"))
      (node (ref "U6") (pin "5") (pinfunction "OUT_B_5") (pintype "passive"))
    )
    (net (code "76") (name "Net-(U7-OUT_A)") (class "Default")
      (node (ref "R36") (pin "1") (pinfunction "1_1") (pintype "passive"))
      (node (ref "U7") (pin "7") (pinfunction "OUT_A_7") (pintype "passive"))
    )
    (net (code "77") (name "Net-(U7-OUT_B)") (class "Default")
      (node (ref "R35") (pin "2") (pinfunction "2_2") (pintype "passive"))
      (node (ref "U7") (pin "5") (pinfunction "OUT_B_5") (pintype "passive"))
    )
    (net (code "78") (name "unconnected-(K1-PadNC)") (class "Default")
      (node (ref "K1") (pin "NC") (pinfunction "NC_NC") (pintype "passive"))
    )
    (net (code "79") (name "unconnected-(K2-PadNC)") (class "Default")
      (node (ref "K2") (pin "NC") (pinfunction "NC_NC") (pintype "passive"))
    )
    (net (code "80") (name "unconnected-(U6-NC-Pad8)") (class "Default")
      (node (ref "U6") (pin "8") (pinfunction "NC_8") (pintype "passive"))
    )
    (net (code "81") (name "unconnected-(U6-NC_2-Pad1)") (class "Default")
      (node (ref "U6") (pin "1") (pinfunction "NC_2_1") (pintype "passive"))
    )
    (net (code "82") (name "unconnected-(U7-NC-Pad8)") (class "Default")
      (node (ref "U7") (pin "8") (pinfunction "NC_8") (pintype "passive"))
    )
    (net (code "83") (name "unconnected-(U7-NC_2-Pad1)") (class "Default")
      (node (ref "U7") (pin "1") (pinfunction "NC_2_1") (pintype "passive"))
    )
  )
)
